# TeensyROM.net
KiCad netlist of a schematic drawn in EAGLE
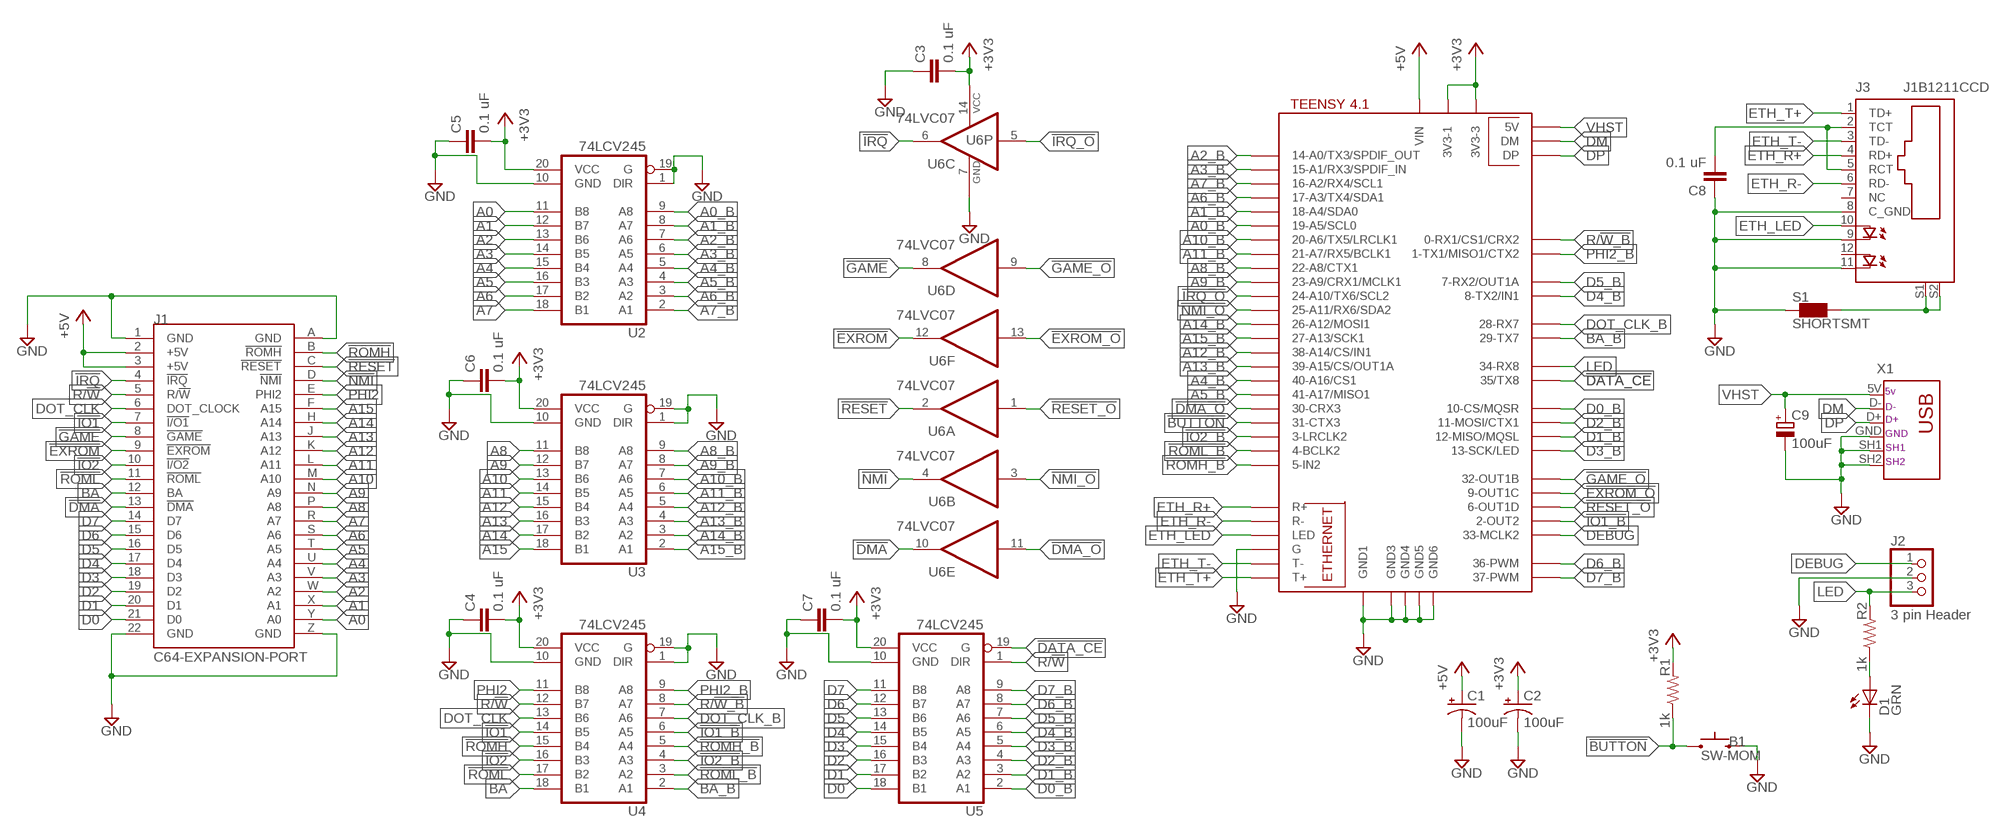
[diagram p0: schematic, sheet 1]

(export (version "E")
  (design (tool "Eeschema 10.0.6"))
  (components
    (comp (ref "B1")
      (value "SW-MOM")
      (footprint "eagle-import:TACTILE-PTH")
      (libsource (lib "eagle-import") (part "SWITCH-MOMENTARY-2PTH"))
    )
    (comp (ref "C1")
      (value "100uF")
      (footprint "eagle-import:E2,5-6")
      (libsource (lib "eagle-import") (part "CPOL-USE2.5-6"))
    )
    (comp (ref "C2")
      (value "100uF")
      (footprint "eagle-import:E2,5-6")
      (libsource (lib "eagle-import") (part "CPOL-USE2.5-6"))
    )
    (comp (ref "C3")
      (value "0.1 uF")
      (footprint "eagle-import:0805")
      (libsource (lib "eagle-import") (part "CAP-0805-0.1UF-50V"))
    )
    (comp (ref "C4")
      (value "0.1 uF")
      (footprint "eagle-import:0805")
      (libsource (lib "eagle-import") (part "CAP-0805-0.1UF-50V"))
    )
    (comp (ref "C5")
      (value "0.1 uF")
      (footprint "eagle-import:0805")
      (libsource (lib "eagle-import") (part "CAP-0805-0.1UF-50V"))
    )
    (comp (ref "C6")
      (value "0.1 uF")
      (footprint "eagle-import:0805")
      (libsource (lib "eagle-import") (part "CAP-0805-0.1UF-50V"))
    )
    (comp (ref "C7")
      (value "0.1 uF")
      (footprint "eagle-import:0805")
      (libsource (lib "eagle-import") (part "CAP-0805-0.1UF-50V"))
    )
    (comp (ref "C8")
      (value "0.1 uF")
      (footprint "eagle-import:0805")
      (libsource (lib "eagle-import") (part "CAP-0805-0.1UF-50V"))
    )
    (comp (ref "C9")
      (value "100uF")
      (footprint "eagle-import:A_3216-18W")
      (libsource (lib "eagle-import") (part "CPOL-EUA/3216-18W"))
    )
    (comp (ref "D1")
      (value "GRN")
      (footprint "eagle-import:LED-3MM-PTH")
      (libsource (lib "eagle-import") (part "LED-3MM-GRN"))
    )
    (comp (ref "J1")
      (value "C64-EXPANSION-PORT")
      (footprint "eagle-import:EXPANSIO_SQ")
      (libsource (lib "eagle-import") (part "C64-EXPANSIONPNARROW"))
    )
    (comp (ref "J2")
      (value "3 pin Header")
      (footprint "eagle-import:1X03")
      (libsource (lib "eagle-import") (part "PINHD-1X3"))
    )
    (comp (ref "J3")
      (value "J1B1211CCD")
      (footprint "eagle-import:CONN12_J1B1211CCD_WIZ")
      (fields (field (name "COPYRIGHT") "Copyright (C) 2023 Ultra Librarian. All rights reserved."))
      (libsource (lib "eagle-import") (part "J1B1211CCD"))
    )
    (comp (ref "R1")
      (value "1k")
      (footprint "eagle-import:R0805")
      (libsource (lib "eagle-import") (part "R-US_R0805"))
    )
    (comp (ref "R2")
      (value "1k")
      (footprint "eagle-import:R0805")
      (libsource (lib "eagle-import") (part "R-US_R0805"))
    )
    (comp (ref "S1")
      (value "SHORTSMT")
      (footprint "eagle-import:SHORT")
      (libsource (lib "eagle-import") (part "SHORTSMT"))
    )
    (comp (ref "U1")
      (value "TEENSY41")
      (footprint "eagle-import:TEENSY41")
      (libsource (lib "eagle-import") (part "TEENSY41"))
    )
    (comp (ref "U2")
      (value "74LCV245")
      (footprint "eagle-import:SO20W")
      (libsource (lib "eagle-import") (part "74245DWLS"))
    )
    (comp (ref "U3")
      (value "74LCV245")
      (footprint "eagle-import:SO20W")
      (libsource (lib "eagle-import") (part "74245DWLS"))
    )
    (comp (ref "U4")
      (value "74LCV245")
      (footprint "eagle-import:SO20W")
      (libsource (lib "eagle-import") (part "74245DWLS"))
    )
    (comp (ref "U5")
      (value "74LCV245")
      (footprint "eagle-import:SO20W")
      (libsource (lib "eagle-import") (part "74245DWLS"))
    )
    (comp (ref "U6")
      (value "74LVC07")
      (footprint "eagle-import:SO14")
      (libsource (lib "eagle-import") (part "7407DLS"))
    )
    (comp (ref "X1")
      (value "USB-787616")
      (footprint "eagle-import:USB")
      (libsource (lib "eagle-import") (part "USB-787616"))
    )
  )
  (nets
    (net (code "1") (name "+3V3") (class "Default")
      (node (ref "C2") (pin "+") (pinfunction "+_+") (pintype "passive"))
      (node (ref "C3") (pin "2") (pinfunction "2_2") (pintype "passive"))
      (node (ref "C4") (pin "2") (pinfunction "2_2") (pintype "passive"))
      (node (ref "C5") (pin "2") (pinfunction "2_2") (pintype "passive"))
      (node (ref "C6") (pin "2") (pinfunction "2_2") (pintype "passive"))
      (node (ref "C7") (pin "2") (pinfunction "2_2") (pintype "passive"))
      (node (ref "R1") (pin "2") (pinfunction "2_2") (pintype "passive"))
      (node (ref "U1") (pin "3V3-1") (pinfunction "3V3-1_3V3-1") (pintype "bidirectional"))
      (node (ref "U1") (pin "3V3-3") (pinfunction "3V3-3_3V3-3") (pintype "bidirectional"))
      (node (ref "U2") (pin "20") (pinfunction "VCC_20") (pintype "bidirectional"))
      (node (ref "U3") (pin "20") (pinfunction "VCC_20") (pintype "bidirectional"))
      (node (ref "U4") (pin "20") (pinfunction "VCC_20") (pintype "bidirectional"))
      (node (ref "U5") (pin "20") (pinfunction "VCC_20") (pintype "bidirectional"))
      (node (ref "U6") (pin "14") (pinfunction "VCC_14") (pintype "power_in"))
    )
    (net (code "2") (name "+5V") (class "Default")
      (node (ref "C1") (pin "+") (pinfunction "+_+") (pintype "passive"))
      (node (ref "J1") (pin "2") (pinfunction "+5V_2") (pintype "power_in"))
      (node (ref "J1") (pin "3") (pinfunction "+5V_3") (pintype "power_in"))
      (node (ref "U1") (pin "VIN") (pinfunction "VIN_VIN") (pintype "bidirectional"))
    )
    (net (code "3") (name "/R{slash}~{W_B}") (class "Default")
      (node (ref "U1") (pin "0-RX1/CS1/CRX2") (pinfunction "0-RX1/CS1/CRX2_0-RX1/CS1/CRX2") (pintype "bidirectional"))
      (node (ref "U4") (pin "8") (pinfunction "A7_8") (pintype "bidirectional"))
    )
    (net (code "4") (name "/R{slash}~{W}") (class "Default")
      (node (ref "J1") (pin "5") (pinfunction "R/~{W}_5") (pintype "output"))
      (node (ref "U4") (pin "12") (pinfunction "B7_12") (pintype "bidirectional"))
      (node (ref "U5") (pin "1") (pinfunction "DIR_1") (pintype "input"))
    )
    (net (code "5") (name "/~{BUTTON}") (class "Default")
      (node (ref "B1") (pin "1") (pinfunction "1_1") (pintype "passive"))
      (node (ref "R1") (pin "1") (pinfunction "1_1") (pintype "passive"))
      (node (ref "U1") (pin "31-CTX3") (pinfunction "31-CTX3_31-CTX3") (pintype "bidirectional"))
    )
    (net (code "6") (name "/~{DATA_CE}") (class "Default")
      (node (ref "U1") (pin "35-TX8") (pinfunction "35/TX8_35-TX8") (pintype "bidirectional"))
      (node (ref "U5") (pin "19") (pinfunction "G_19") (pintype "input"))
    )
    (net (code "7") (name "/~{DMA_O}") (class "Default")
      (node (ref "U1") (pin "30-CRX3") (pinfunction "30-CRX3_30-CRX3") (pintype "bidirectional"))
      (node (ref "U6") (pin "11") (pinfunction "I_11") (pintype "input"))
    )
    (net (code "8") (name "/~{DMA}") (class "Default")
      (node (ref "J1") (pin "13") (pinfunction "~{DMA}_13") (pintype "input"))
      (node (ref "U6") (pin "10") (pinfunction "O_10") (pintype "open_collector"))
    )
    (net (code "9") (name "/~{EXROM_O}") (class "Default")
      (node (ref "U1") (pin "9-OUT1C") (pinfunction "9-OUT1C_9-OUT1C") (pintype "bidirectional"))
      (node (ref "U6") (pin "13") (pinfunction "I_13") (pintype "input"))
    )
    (net (code "10") (name "/~{EXROM}") (class "Default")
      (node (ref "J1") (pin "9") (pinfunction "~{EXROM}_9") (pintype "input"))
      (node (ref "U6") (pin "12") (pinfunction "O_12") (pintype "open_collector"))
    )
    (net (code "11") (name "/~{GAME_O}") (class "Default")
      (node (ref "U1") (pin "32-OUT1B") (pinfunction "32-OUT1B_32-OUT1B") (pintype "bidirectional"))
      (node (ref "U6") (pin "9") (pinfunction "I_9") (pintype "input"))
    )
    (net (code "12") (name "/~{GAME}") (class "Default")
      (node (ref "J1") (pin "8") (pinfunction "~{GAME}_8") (pintype "input"))
      (node (ref "U6") (pin "8") (pinfunction "O_8") (pintype "open_collector"))
    )
    (net (code "13") (name "/~{IO1_B}") (class "Default")
      (node (ref "U1") (pin "2-OUT2") (pinfunction "2-OUT2_2-OUT2") (pintype "bidirectional"))
      (node (ref "U4") (pin "6") (pinfunction "A5_6") (pintype "bidirectional"))
    )
    (net (code "14") (name "/~{IO1}") (class "Default")
      (node (ref "J1") (pin "7") (pinfunction "~{I/O1}_7") (pintype "output"))
      (node (ref "U4") (pin "14") (pinfunction "B5_14") (pintype "bidirectional"))
    )
    (net (code "15") (name "/~{IO2_B}") (class "Default")
      (node (ref "U1") (pin "3-LRCLK2") (pinfunction "3-LRCLK2_3-LRCLK2") (pintype "bidirectional"))
      (node (ref "U4") (pin "4") (pinfunction "A3_4") (pintype "bidirectional"))
    )
    (net (code "16") (name "/~{IO2}") (class "Default")
      (node (ref "J1") (pin "10") (pinfunction "~{I/O2}_10") (pintype "output"))
      (node (ref "U4") (pin "16") (pinfunction "B3_16") (pintype "bidirectional"))
    )
    (net (code "17") (name "/~{IRQ_O}") (class "Default")
      (node (ref "U1") (pin "24-A10/TX6/SCL2") (pinfunction "24-A10/TX6/SCL2_24-A10/TX6/SCL2") (pintype "bidirectional"))
      (node (ref "U6") (pin "5") (pinfunction "I_5") (pintype "input"))
    )
    (net (code "18") (name "/~{IRQ}") (class "Default")
      (node (ref "J1") (pin "4") (pinfunction "~{IRQ}_4") (pintype "input"))
      (node (ref "U6") (pin "6") (pinfunction "O_6") (pintype "open_collector"))
    )
    (net (code "19") (name "/~{NMI_O}") (class "Default")
      (node (ref "U1") (pin "25-A11/RX6/SDA2") (pinfunction "25-A11/RX6/SDA2_25-A11/RX6/SDA2") (pintype "bidirectional"))
      (node (ref "U6") (pin "3") (pinfunction "I_3") (pintype "input"))
    )
    (net (code "20") (name "/~{NMI}") (class "Default")
      (node (ref "J1") (pin "D") (pinfunction "~{NMI}_D") (pintype "input"))
      (node (ref "U6") (pin "4") (pinfunction "O_4") (pintype "open_collector"))
    )
    (net (code "21") (name "/~{RESET_O}") (class "Default")
      (node (ref "U1") (pin "6-OUT1D") (pinfunction "6-OUT1D_6-OUT1D") (pintype "bidirectional"))
      (node (ref "U6") (pin "1") (pinfunction "I_1") (pintype "input"))
    )
    (net (code "22") (name "/~{RESET}") (class "Default")
      (node (ref "J1") (pin "C") (pinfunction "~{RESET}_C") (pintype "open_collector"))
      (node (ref "U6") (pin "2") (pinfunction "O_2") (pintype "open_collector"))
    )
    (net (code "23") (name "/~{ROMH_B}") (class "Default")
      (node (ref "U1") (pin "5-IN2") (pinfunction "5-IN2_5-IN2") (pintype "bidirectional"))
      (node (ref "U4") (pin "5") (pinfunction "A4_5") (pintype "bidirectional"))
    )
    (net (code "24") (name "/~{ROMH}") (class "Default")
      (node (ref "J1") (pin "B") (pinfunction "~{ROMH}_B") (pintype "output"))
      (node (ref "U4") (pin "15") (pinfunction "B4_15") (pintype "bidirectional"))
    )
    (net (code "25") (name "/~{ROML_B}") (class "Default")
      (node (ref "U1") (pin "4-BCLK2") (pinfunction "4-BCLK2_4-BCLK2") (pintype "bidirectional"))
      (node (ref "U4") (pin "3") (pinfunction "A2_3") (pintype "bidirectional"))
    )
    (net (code "26") (name "/~{ROML}") (class "Default")
      (node (ref "J1") (pin "11") (pinfunction "~{ROML}_11") (pintype "output"))
      (node (ref "U4") (pin "17") (pinfunction "B2_17") (pintype "bidirectional"))
    )
    (net (code "27") (name "A0") (class "Default")
      (node (ref "J1") (pin "Y") (pinfunction "A0_Y") (pintype "bidirectional"))
      (node (ref "U2") (pin "11") (pinfunction "B8_11") (pintype "bidirectional"))
    )
    (net (code "28") (name "A0_B") (class "Default")
      (node (ref "U1") (pin "19-A5/SCL0") (pinfunction "19-A5/SCL0_19-A5/SCL0") (pintype "bidirectional"))
      (node (ref "U2") (pin "9") (pinfunction "A8_9") (pintype "bidirectional"))
    )
    (net (code "29") (name "A1") (class "Default")
      (node (ref "J1") (pin "X") (pinfunction "A1_X") (pintype "bidirectional"))
      (node (ref "U2") (pin "12") (pinfunction "B7_12") (pintype "bidirectional"))
    )
    (net (code "30") (name "A1_B") (class "Default")
      (node (ref "U1") (pin "18-A4/SDA0") (pinfunction "18-A4/SDA0_18-A4/SDA0") (pintype "bidirectional"))
      (node (ref "U2") (pin "8") (pinfunction "A7_8") (pintype "bidirectional"))
    )
    (net (code "31") (name "A2") (class "Default")
      (node (ref "J1") (pin "W") (pinfunction "A2_W") (pintype "bidirectional"))
      (node (ref "U2") (pin "13") (pinfunction "B6_13") (pintype "bidirectional"))
    )
    (net (code "32") (name "A2_B") (class "Default")
      (node (ref "U1") (pin "14-A0/TX3/SPDIF_OUT") (pinfunction "14-A0/TX3/SPDIF_OUT_14-A0/TX3/SPDIF_OUT") (pintype "bidirectional"))
      (node (ref "U2") (pin "7") (pinfunction "A6_7") (pintype "bidirectional"))
    )
    (net (code "33") (name "A3") (class "Default")
      (node (ref "J1") (pin "V") (pinfunction "A3_V") (pintype "bidirectional"))
      (node (ref "U2") (pin "14") (pinfunction "B5_14") (pintype "bidirectional"))
    )
    (net (code "34") (name "A3_B") (class "Default")
      (node (ref "U1") (pin "15-A1/RX3/SPDIF_IN") (pinfunction "15-A1/RX3/SPDIF_IN_15-A1/RX3/SPDIF_IN") (pintype "bidirectional"))
      (node (ref "U2") (pin "6") (pinfunction "A5_6") (pintype "bidirectional"))
    )
    (net (code "35") (name "A4") (class "Default")
      (node (ref "J1") (pin "U") (pinfunction "A4_U") (pintype "bidirectional"))
      (node (ref "U2") (pin "15") (pinfunction "B4_15") (pintype "bidirectional"))
    )
    (net (code "36") (name "A4_B") (class "Default")
      (node (ref "U1") (pin "40-A16/CS1") (pinfunction "40-A16/CS1_40-A16/CS1") (pintype "bidirectional"))
      (node (ref "U2") (pin "5") (pinfunction "A4_5") (pintype "bidirectional"))
    )
    (net (code "37") (name "A5") (class "Default")
      (node (ref "J1") (pin "T") (pinfunction "A5_T") (pintype "bidirectional"))
      (node (ref "U2") (pin "16") (pinfunction "B3_16") (pintype "bidirectional"))
    )
    (net (code "38") (name "A5_B") (class "Default")
      (node (ref "U1") (pin "41-A17/MISO1") (pinfunction "41-A17/MISO1_41-A17/MISO1") (pintype "bidirectional"))
      (node (ref "U2") (pin "4") (pinfunction "A3_4") (pintype "bidirectional"))
    )
    (net (code "39") (name "A6") (class "Default")
      (node (ref "J1") (pin "S") (pinfunction "A6_S") (pintype "bidirectional"))
      (node (ref "U2") (pin "17") (pinfunction "B2_17") (pintype "bidirectional"))
    )
    (net (code "40") (name "A6_B") (class "Default")
      (node (ref "U1") (pin "17-A3/TX4/SDA1") (pinfunction "17-A3/TX4/SDA1_17-A3/TX4/SDA1") (pintype "bidirectional"))
      (node (ref "U2") (pin "3") (pinfunction "A2_3") (pintype "bidirectional"))
    )
    (net (code "41") (name "A7") (class "Default")
      (node (ref "J1") (pin "R") (pinfunction "A7_R") (pintype "bidirectional"))
      (node (ref "U2") (pin "18") (pinfunction "B1_18") (pintype "bidirectional"))
    )
    (net (code "42") (name "A7_B") (class "Default")
      (node (ref "U1") (pin "16-A2/RX4/SCL1") (pinfunction "16-A2/RX4/SCL1_16-A2/RX4/SCL1") (pintype "bidirectional"))
      (node (ref "U2") (pin "2") (pinfunction "A1_2") (pintype "bidirectional"))
    )
    (net (code "43") (name "A8") (class "Default")
      (node (ref "J1") (pin "P") (pinfunction "A8_P") (pintype "bidirectional"))
      (node (ref "U3") (pin "11") (pinfunction "B8_11") (pintype "bidirectional"))
    )
    (net (code "44") (name "A8_B") (class "Default")
      (node (ref "U1") (pin "22-A8/CTX1") (pinfunction "22-A8/CTX1_22-A8/CTX1") (pintype "bidirectional"))
      (node (ref "U3") (pin "9") (pinfunction "A8_9") (pintype "bidirectional"))
    )
    (net (code "45") (name "A9") (class "Default")
      (node (ref "J1") (pin "N") (pinfunction "A9_N") (pintype "bidirectional"))
      (node (ref "U3") (pin "12") (pinfunction "B7_12") (pintype "bidirectional"))
    )
    (net (code "46") (name "A9_B") (class "Default")
      (node (ref "U1") (pin "23-A9/CRX1/MCLK1") (pinfunction "23-A9/CRX1/MCLK1_23-A9/CRX1/MCLK1") (pintype "bidirectional"))
      (node (ref "U3") (pin "8") (pinfunction "A7_8") (pintype "bidirectional"))
    )
    (net (code "47") (name "A10") (class "Default")
      (node (ref "J1") (pin "M") (pinfunction "A10_M") (pintype "bidirectional"))
      (node (ref "U3") (pin "13") (pinfunction "B6_13") (pintype "bidirectional"))
    )
    (net (code "48") (name "A10_B") (class "Default")
      (node (ref "U1") (pin "20-A6/TX5/LRCLK1") (pinfunction "20-A6/TX5/LRCLK1_20-A6/TX5/LRCLK1") (pintype "bidirectional"))
      (node (ref "U3") (pin "7") (pinfunction "A6_7") (pintype "bidirectional"))
    )
    (net (code "49") (name "A11") (class "Default")
      (node (ref "J1") (pin "L") (pinfunction "A11_L") (pintype "bidirectional"))
      (node (ref "U3") (pin "14") (pinfunction "B5_14") (pintype "bidirectional"))
    )
    (net (code "50") (name "A11_B") (class "Default")
      (node (ref "U1") (pin "21-A7/RX5/BCLK1") (pinfunction "21-A7/RX5/BCLK1_21-A7/RX5/BCLK1") (pintype "bidirectional"))
      (node (ref "U3") (pin "6") (pinfunction "A5_6") (pintype "bidirectional"))
    )
    (net (code "51") (name "A12") (class "Default")
      (node (ref "J1") (pin "K") (pinfunction "A12_K") (pintype "bidirectional"))
      (node (ref "U3") (pin "15") (pinfunction "B4_15") (pintype "bidirectional"))
    )
    (net (code "52") (name "A12_B") (class "Default")
      (node (ref "U1") (pin "38-A14/CS/IN1") (pinfunction "38-A14/CS/IN1_38-A14/CS/IN1") (pintype "bidirectional"))
      (node (ref "U3") (pin "5") (pinfunction "A4_5") (pintype "bidirectional"))
    )
    (net (code "53") (name "A13") (class "Default")
      (node (ref "J1") (pin "J") (pinfunction "A13_J") (pintype "bidirectional"))
      (node (ref "U3") (pin "16") (pinfunction "B3_16") (pintype "bidirectional"))
    )
    (net (code "54") (name "A13_B") (class "Default")
      (node (ref "U1") (pin "39-A15/CS/OUT1A") (pinfunction "39-A15/CS/OUT1A_39-A15/CS/OUT1A") (pintype "bidirectional"))
      (node (ref "U3") (pin "4") (pinfunction "A3_4") (pintype "bidirectional"))
    )
    (net (code "55") (name "A14") (class "Default")
      (node (ref "J1") (pin "H") (pinfunction "A14_H") (pintype "bidirectional"))
      (node (ref "U3") (pin "17") (pinfunction "B2_17") (pintype "bidirectional"))
    )
    (net (code "56") (name "A14_B") (class "Default")
      (node (ref "U1") (pin "26-A12/MOSI1") (pinfunction "26-A12/MOSI1_26-A12/MOSI1") (pintype "bidirectional"))
      (node (ref "U3") (pin "3") (pinfunction "A2_3") (pintype "bidirectional"))
    )
    (net (code "57") (name "A15") (class "Default")
      (node (ref "J1") (pin "F") (pinfunction "A15_F") (pintype "bidirectional"))
      (node (ref "U3") (pin "18") (pinfunction "B1_18") (pintype "bidirectional"))
    )
    (net (code "58") (name "A15_B") (class "Default")
      (node (ref "U1") (pin "27-A13/SCK1") (pinfunction "27-A13/SCK1_27-A13/SCK1") (pintype "bidirectional"))
      (node (ref "U3") (pin "2") (pinfunction "A1_2") (pintype "bidirectional"))
    )
    (net (code "59") (name "BA") (class "Default")
      (node (ref "J1") (pin "12") (pinfunction "BA_12") (pintype "output"))
      (node (ref "U4") (pin "18") (pinfunction "B1_18") (pintype "bidirectional"))
    )
    (net (code "60") (name "BA_B") (class "Default")
      (node (ref "U1") (pin "29-TX7") (pinfunction "29-TX7_29-TX7") (pintype "bidirectional"))
      (node (ref "U4") (pin "2") (pinfunction "A1_2") (pintype "bidirectional"))
    )
    (net (code "61") (name "D0") (class "Default")
      (node (ref "J1") (pin "21") (pinfunction "D0_21") (pintype "bidirectional"))
      (node (ref "U5") (pin "18") (pinfunction "B1_18") (pintype "bidirectional"))
    )
    (net (code "62") (name "D0_B") (class "Default")
      (node (ref "U1") (pin "10-CS\\MQSR") (pinfunction "10-CS/MQSR_10-CS\\MQSR") (pintype "bidirectional"))
      (node (ref "U5") (pin "2") (pinfunction "A1_2") (pintype "bidirectional"))
    )
    (net (code "63") (name "D1") (class "Default")
      (node (ref "J1") (pin "20") (pinfunction "D1_20") (pintype "bidirectional"))
      (node (ref "U5") (pin "17") (pinfunction "B2_17") (pintype "bidirectional"))
    )
    (net (code "64") (name "D1_B") (class "Default")
      (node (ref "U1") (pin "12-MISO/MQSL") (pinfunction "12-MISO/MQSL_12-MISO/MQSL") (pintype "bidirectional"))
      (node (ref "U5") (pin "3") (pinfunction "A2_3") (pintype "bidirectional"))
    )
    (net (code "65") (name "D2") (class "Default")
      (node (ref "J1") (pin "19") (pinfunction "D2_19") (pintype "bidirectional"))
      (node (ref "U5") (pin "16") (pinfunction "B3_16") (pintype "bidirectional"))
    )
    (net (code "66") (name "D2_B") (class "Default")
      (node (ref "U1") (pin "11-MOSI/CTX1") (pinfunction "11-MOSI/CTX1_11-MOSI/CTX1") (pintype "bidirectional"))
      (node (ref "U5") (pin "4") (pinfunction "A3_4") (pintype "bidirectional"))
    )
    (net (code "67") (name "D3") (class "Default")
      (node (ref "J1") (pin "18") (pinfunction "D3_18") (pintype "bidirectional"))
      (node (ref "U5") (pin "15") (pinfunction "B4_15") (pintype "bidirectional"))
    )
    (net (code "68") (name "D3_B") (class "Default")
      (node (ref "U1") (pin "13-SCK/LED") (pinfunction "13-SCK/LED_13-SCK/LED") (pintype "bidirectional"))
      (node (ref "U5") (pin "5") (pinfunction "A4_5") (pintype "bidirectional"))
    )
    (net (code "69") (name "D4") (class "Default")
      (node (ref "J1") (pin "17") (pinfunction "D4_17") (pintype "bidirectional"))
      (node (ref "U5") (pin "14") (pinfunction "B5_14") (pintype "bidirectional"))
    )
    (net (code "70") (name "D4_B") (class "Default")
      (node (ref "U1") (pin "8-TX2/IN1") (pinfunction "8-TX2/IN1_8-TX2/IN1") (pintype "bidirectional"))
      (node (ref "U5") (pin "6") (pinfunction "A5_6") (pintype "bidirectional"))
    )
    (net (code "71") (name "D5") (class "Default")
      (node (ref "J1") (pin "16") (pinfunction "D5_16") (pintype "bidirectional"))
      (node (ref "U5") (pin "13") (pinfunction "B6_13") (pintype "bidirectional"))
    )
    (net (code "72") (name "D5_B") (class "Default")
      (node (ref "U1") (pin "7-RX2/OUT1A") (pinfunction "7-RX2/OUT1A_7-RX2/OUT1A") (pintype "bidirectional"))
      (node (ref "U5") (pin "7") (pinfunction "A6_7") (pintype "bidirectional"))
    )
    (net (code "73") (name "D6") (class "Default")
      (node (ref "J1") (pin "15") (pinfunction "D6_15") (pintype "bidirectional"))
      (node (ref "U5") (pin "12") (pinfunction "B7_12") (pintype "bidirectional"))
    )
    (net (code "74") (name "D6_B") (class "Default")
      (node (ref "U1") (pin "36-PWM") (pinfunction "36-PWM_36-PWM") (pintype "bidirectional"))
      (node (ref "U5") (pin "8") (pinfunction "A7_8") (pintype "bidirectional"))
    )
    (net (code "75") (name "D7") (class "Default")
      (node (ref "J1") (pin "14") (pinfunction "D7_14") (pintype "bidirectional"))
      (node (ref "U5") (pin "11") (pinfunction "B8_11") (pintype "bidirectional"))
    )
    (net (code "76") (name "D7_B") (class "Default")
      (node (ref "U1") (pin "37-PWM") (pinfunction "37-PWM_37-PWM") (pintype "bidirectional"))
      (node (ref "U5") (pin "9") (pinfunction "A8_9") (pintype "bidirectional"))
    )
    (net (code "77") (name "DEBUG") (class "Default")
      (node (ref "J2") (pin "1") (pinfunction "1_1") (pintype "passive"))
      (node (ref "U1") (pin "33-MCLK2") (pinfunction "33-MCLK2_33-MCLK2") (pintype "bidirectional"))
    )
    (net (code "78") (name "DM") (class "Default")
      (node (ref "U1") (pin "DM") (pinfunction "DM_DM") (pintype "bidirectional"))
      (node (ref "X1") (pin "D-") (pinfunction "2_D-") (pintype "passive"))
    )
    (net (code "79") (name "DOT_CLK") (class "Default")
      (node (ref "J1") (pin "6") (pinfunction "DOT_CLOCK_6") (pintype "output"))
      (node (ref "U4") (pin "13") (pinfunction "B6_13") (pintype "bidirectional"))
    )
    (net (code "80") (name "DOT_CLK_B") (class "Default")
      (node (ref "U1") (pin "28-RX7") (pinfunction "28-RX7_28-RX7") (pintype "bidirectional"))
      (node (ref "U4") (pin "7") (pinfunction "A6_7") (pintype "bidirectional"))
    )
    (net (code "81") (name "DP") (class "Default")
      (node (ref "U1") (pin "DP") (pinfunction "DP_DP") (pintype "bidirectional"))
      (node (ref "X1") (pin "D+") (pinfunction "3_D+") (pintype "passive"))
    )
    (net (code "82") (name "ETH_LED") (class "Default")
      (node (ref "J3") (pin "10") (pinfunction "A_10") (pintype "passive"))
      (node (ref "U1") (pin "LED") (pinfunction "LED_LED") (pintype "bidirectional"))
    )
    (net (code "83") (name "ETH_R+") (class "Default")
      (node (ref "J3") (pin "4") (pinfunction "RD+_4") (pintype "passive"))
      (node (ref "U1") (pin "R+") (pinfunction "R+_R+") (pintype "bidirectional"))
    )
    (net (code "84") (name "ETH_R-") (class "Default")
      (node (ref "J3") (pin "6") (pinfunction "RD-_6") (pintype "passive"))
      (node (ref "U1") (pin "R-") (pinfunction "R-_R-") (pintype "bidirectional"))
    )
    (net (code "85") (name "ETH_T+") (class "Default")
      (node (ref "J3") (pin "1") (pinfunction "TD+_1") (pintype "passive"))
      (node (ref "U1") (pin "T+") (pinfunction "T+_T+") (pintype "bidirectional"))
    )
    (net (code "86") (name "ETH_T-") (class "Default")
      (node (ref "J3") (pin "3") (pinfunction "TD-_3") (pintype "passive"))
      (node (ref "U1") (pin "T-") (pinfunction "T-_T-") (pintype "bidirectional"))
    )
    (net (code "87") (name "GND") (class "Default")
      (node (ref "B1") (pin "3") (pinfunction "2_3") (pintype "passive"))
      (node (ref "C1") (pin "-") (pinfunction "-_-") (pintype "passive"))
      (node (ref "C2") (pin "-") (pinfunction "-_-") (pintype "passive"))
      (node (ref "C3") (pin "1") (pinfunction "1_1") (pintype "passive"))
      (node (ref "C4") (pin "1") (pinfunction "1_1") (pintype "passive"))
      (node (ref "C5") (pin "1") (pinfunction "1_1") (pintype "passive"))
      (node (ref "C6") (pin "1") (pinfunction "1_1") (pintype "passive"))
      (node (ref "C7") (pin "1") (pinfunction "1_1") (pintype "passive"))
      (node (ref "C8") (pin "1") (pinfunction "1_1") (pintype "passive"))
      (node (ref "C9") (pin "-") (pinfunction "-_-") (pintype "passive"))
      (node (ref "D1") (pin "K") (pinfunction "C_K") (pintype "passive"))
      (node (ref "J1") (pin "1") (pinfunction "GND_1") (pintype "power_in"))
      (node (ref "J1") (pin "22") (pinfunction "GND_22") (pintype "power_in"))
      (node (ref "J1") (pin "A") (pinfunction "GND_A") (pintype "power_in"))
      (node (ref "J1") (pin "Z") (pinfunction "GND_Z") (pintype "power_in"))
      (node (ref "J2") (pin "2") (pinfunction "2_2") (pintype "passive"))
      (node (ref "J3") (pin "11") (pinfunction "C1_11") (pintype "passive"))
      (node (ref "J3") (pin "8") (pinfunction "C_GND_8") (pintype "passive"))
      (node (ref "J3") (pin "9") (pinfunction "C_9") (pintype "passive"))
      (node (ref "S1") (pin "1") (pinfunction "1_1") (pintype "passive"))
      (node (ref "U1") (pin "G") (pinfunction "G_G") (pintype "bidirectional"))
      (node (ref "U1") (pin "GND1") (pinfunction "GND1_GND1") (pintype "bidirectional"))
      (node (ref "U1") (pin "GND3") (pinfunction "GND3_GND3") (pintype "bidirectional"))
      (node (ref "U1") (pin "GND4") (pinfunction "GND4_GND4") (pintype "bidirectional"))
      (node (ref "U1") (pin "GND5") (pinfunction "GND5_GND5") (pintype "bidirectional"))
      (node (ref "U1") (pin "GND6") (pinfunction "GND6_GND6") (pintype "bidirectional"))
      (node (ref "U2") (pin "1") (pinfunction "DIR_1") (pintype "input"))
      (node (ref "U2") (pin "10") (pinfunction "GND_10") (pintype "bidirectional"))
      (node (ref "U2") (pin "19") (pinfunction "G_19") (pintype "input"))
      (node (ref "U3") (pin "1") (pinfunction "DIR_1") (pintype "input"))
      (node (ref "U3") (pin "10") (pinfunction "GND_10") (pintype "bidirectional"))
      (node (ref "U3") (pin "19") (pinfunction "G_19") (pintype "input"))
      (node (ref "U4") (pin "1") (pinfunction "DIR_1") (pintype "input"))
      (node (ref "U4") (pin "10") (pinfunction "GND_10") (pintype "bidirectional"))
      (node (ref "U4") (pin "19") (pinfunction "G_19") (pintype "input"))
      (node (ref "U5") (pin "10") (pinfunction "GND_10") (pintype "bidirectional"))
      (node (ref "U6") (pin "7") (pinfunction "GND_7") (pintype "power_in"))
      (node (ref "X1") (pin "GND") (pinfunction "4_GND") (pintype "passive"))
      (node (ref "X1") (pin "SH1") (pinfunction "5_SH1") (pintype "passive"))
      (node (ref "X1") (pin "SH2") (pinfunction "6_SH2") (pintype "passive"))
    )
    (net (code "88") (name "LED") (class "Default")
      (node (ref "J2") (pin "3") (pinfunction "3_3") (pintype "passive"))
      (node (ref "R2") (pin "2") (pinfunction "2_2") (pintype "passive"))
      (node (ref "U1") (pin "34-RX8") (pinfunction "34-RX8_34-RX8") (pintype "bidirectional"))
    )
    (net (code "89") (name "Net-(D1-PadA)") (class "Default")
      (node (ref "D1") (pin "A") (pinfunction "A_A") (pintype "passive"))
      (node (ref "R2") (pin "1") (pinfunction "1_1") (pintype "passive"))
    )
    (net (code "90") (name "Net-(J3-PadS1)") (class "Default")
      (node (ref "J3") (pin "S1") (pinfunction "S1_S1") (pintype "passive"))
      (node (ref "J3") (pin "S2") (pinfunction "S2_S2") (pintype "passive"))
      (node (ref "S1") (pin "2") (pinfunction "2_2") (pintype "passive"))
    )
    (net (code "91") (name "Net-(J3-RCT)") (class "Default")
      (node (ref "C8") (pin "2") (pinfunction "2_2") (pintype "passive"))
      (node (ref "J3") (pin "2") (pinfunction "TCT_2") (pintype "passive"))
      (node (ref "J3") (pin "5") (pinfunction "RCT_5") (pintype "passive"))
    )
    (net (code "92") (name "PHI2") (class "Default")
      (node (ref "J1") (pin "E") (pinfunction "PHI2_E") (pintype "output"))
      (node (ref "U4") (pin "11") (pinfunction "B8_11") (pintype "bidirectional"))
    )
    (net (code "93") (name "PHI2_B") (class "Default")
      (node (ref "U1") (pin "1-TX1/MISO1/CTX2") (pinfunction "1-TX1/MISO1/CTX2_1-TX1/MISO1/CTX2") (pintype "bidirectional"))
      (node (ref "U4") (pin "9") (pinfunction "A8_9") (pintype "bidirectional"))
    )
    (net (code "94") (name "VHST") (class "Default")
      (node (ref "C9") (pin "+") (pinfunction "+_+") (pintype "passive"))
      (node (ref "U1") (pin "+5V") (pinfunction "5V_+5V") (pintype "bidirectional"))
      (node (ref "X1") (pin "5V") (pinfunction "1_5V") (pintype "passive"))
    )
    (net (code "95") (name "unconnected-(J3-A1-Pad12)") (class "Default")
      (node (ref "J3") (pin "12") (pinfunction "A1_12") (pintype "passive"))
    )
    (net (code "96") (name "unconnected-(J3-NC-Pad7)") (class "Default")
      (node (ref "J3") (pin "7") (pinfunction "NC_7") (pintype "passive"))
    )
  )
)
